# 2016-02-21_13-02-55.net
KiCad netlist of a schematic drawn in Altium Designer
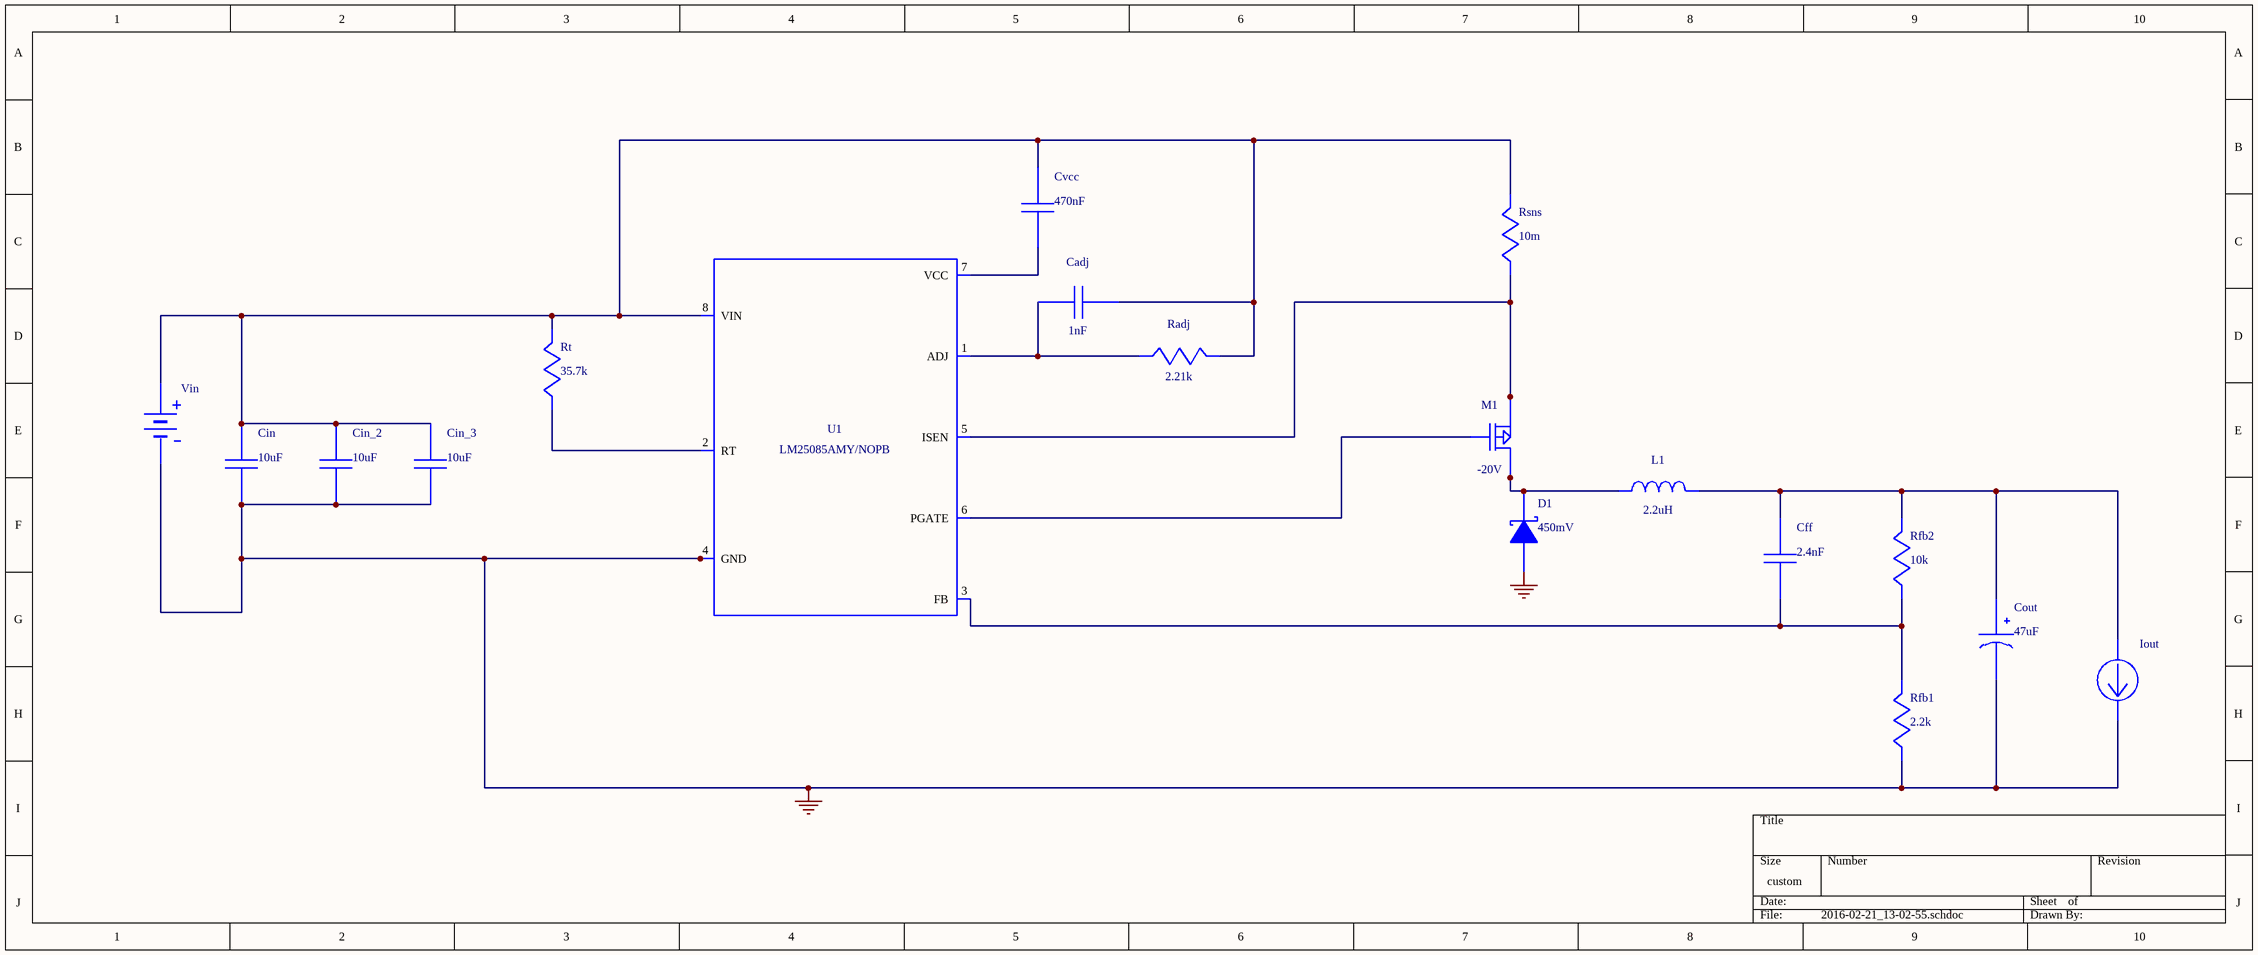
[diagram p0: 2016-02-21_13-02-55.schdoc]

(export (version "E")
  (design (tool "Eeschema 10.0.6"))
  (components
    (comp (ref "Cadj")
      (value "1nF")
      (description "CL21C102JBCNFNC")
      (libsource (lib "TI WEBENCH") (part "Cadj"))
    )
    (comp (ref "Cff")
      (value "2.4nF")
      (description "GRM1885C1H242JA0")
      (fields (field (name "MANUFACTURER PART NUMBER") "GRM1885C1H242JA01D"))
      (libsource (lib "TI WEBENCH") (part "Cff"))
    )
    (comp (ref "Cin")
      (value "10uF")
      (description "GRM21BR61C106KE1")
      (fields (field (name "MANUFACTURER PART NUMBER") "GRM21BR61C106KE15L"))
      (libsource (lib "TI WEBENCH") (part "Cin"))
    )
    (comp (ref "Cin_2")
      (value "10uF")
      (description "GRM21BR61C106KE1")
      (fields (field (name "MANUFACTURER PART NUMBER") "GRM21BR61C106KE15L"))
      (libsource (lib "TI WEBENCH") (part "Cin_2"))
    )
    (comp (ref "Cin_3")
      (value "10uF")
      (description "GRM21BR61C106KE1")
      (fields (field (name "MANUFACTURER PART NUMBER") "GRM21BR61C106KE15L"))
      (libsource (lib "TI WEBENCH") (part "Cin_3"))
    )
    (comp (ref "Cout") (value "47uF") (description "6TPU47MSI") (libsource (lib "TI WEBENCH") (part "Cout")))
    (comp (ref "Cvcc")
      (value "470nF")
      (description "0805YC474KAT2A")
      (libsource (lib "TI WEBENCH") (part "Cvcc"))
    )
    (comp (ref "D1") (value "450mV") (description "B340LA-13-F") (libsource (lib "TI WEBENCH") (part "D1")))
    (comp (ref "Iout") (value "WB_CURRENT_LOAD") (libsource (lib "TI WEBENCH") (part "Iout")))
    (comp (ref "L1")
      (value "2.2uH")
      (description "Unknown")
      (fields (field (name "MANUFACTURER PART NUMBER") "74437368022"))
      (libsource (lib "TI WEBENCH") (part "L1"))
    )
    (comp (ref "M1") (value "-20V") (description "CSD25402Q3A") (libsource (lib "TI WEBENCH") (part "M1")))
    (comp (ref "Radj")
      (value "2.21k")
      (description "CRCW04022K21FKED")
      (libsource (lib "TI WEBENCH") (part "Radj"))
    )
    (comp (ref "Rfb1")
      (value "2.2k")
      (description "RC0603FR-072K2L")
      (libsource (lib "TI WEBENCH") (part "Rfb1"))
    )
    (comp (ref "Rfb2")
      (value "10k")
      (description "CRCW040210K0FKED")
      (libsource (lib "TI WEBENCH") (part "Rfb2"))
    )
    (comp (ref "Rsns")
      (value "10m")
      (description "CSR1206FK10L0")
      (libsource (lib "TI WEBENCH") (part "Rsns"))
    )
    (comp (ref "Rt")
      (value "35.7k")
      (description "CRCW040235K7FKED")
      (libsource (lib "TI WEBENCH") (part "Rt"))
    )
    (comp (ref "U1")
      (value "LM5085MY/NOPB")
      (description "LM25085AMY/NOPB")
      (fields (field (name "PACKAGEREFERENCE") "LM25085AMY/NOPB"))
      (libsource (lib "TI WEBENCH") (part "U1"))
    )
    (comp (ref "Vin") (value "WB_BATTERY") (libsource (lib "TI WEBENCH") (part "Vin")))
  )
  (nets
    (net (code "1") (name "0") (class "Default")
      (node (ref "Cin") (pin "2") (pinfunction "2_2") (pintype "passive"))
      (node (ref "Cin_2") (pin "2") (pinfunction "2_2") (pintype "passive"))
      (node (ref "Cin_3") (pin "2") (pinfunction "2_2") (pintype "passive"))
      (node (ref "Cout") (pin "2") (pinfunction "-_2") (pintype "passive"))
      (node (ref "D1") (pin "2") (pinfunction "A_2") (pintype "passive"))
      (node (ref "Iout") (pin "2") (pinfunction "-_2") (pintype "passive"))
      (node (ref "Rfb1") (pin "2") (pinfunction "2_2") (pintype "passive"))
      (node (ref "U1") (pin "4") (pinfunction "GND_4") (pintype "passive"))
      (node (ref "U1") (pin "9") (pinfunction "EP_9") (pintype "passive"))
      (node (ref "Vin") (pin "2") (pinfunction "-_2") (pintype "passive"))
    )
    (net (code "2") (name "Net-(Cout-+)") (class "Default")
      (node (ref "Cff") (pin "1") (pinfunction "1_1") (pintype "passive"))
      (node (ref "Cout") (pin "1") (pinfunction "+_1") (pintype "passive"))
      (node (ref "Iout") (pin "1") (pinfunction "+_1") (pintype "passive"))
      (node (ref "L1") (pin "2") (pinfunction "2_2") (pintype "passive"))
      (node (ref "Rfb2") (pin "1") (pinfunction "1_1") (pintype "passive"))
    )
    (net (code "3") (name "Net-(D1-K)") (class "Default")
      (node (ref "D1") (pin "1") (pinfunction "K_1") (pintype "passive"))
      (node (ref "L1") (pin "1") (pinfunction "1_1") (pintype "passive"))
      (node (ref "M1") (pin "1") (pinfunction "D_1") (pintype "passive"))
      (node (ref "M1") (pin "2") (pinfunction "D_2") (pintype "passive"))
      (node (ref "M1") (pin "3") (pinfunction "D_3") (pintype "passive"))
    )
    (net (code "4") (name "Net-(M1-G)") (class "Default")
      (node (ref "M1") (pin "4") (pinfunction "G_4") (pintype "passive"))
      (node (ref "U1") (pin "6") (pinfunction "PGATE_6") (pintype "passive"))
    )
    (net (code "5") (name "Net-(U1-ADJ)") (class "Default")
      (node (ref "Cadj") (pin "2") (pinfunction "2_2") (pintype "passive"))
      (node (ref "Radj") (pin "2") (pinfunction "2_2") (pintype "passive"))
      (node (ref "U1") (pin "1") (pinfunction "ADJ_1") (pintype "passive"))
    )
    (net (code "6") (name "Net-(U1-FB)") (class "Default")
      (node (ref "Cff") (pin "2") (pinfunction "2_2") (pintype "passive"))
      (node (ref "Rfb1") (pin "1") (pinfunction "1_1") (pintype "passive"))
      (node (ref "Rfb2") (pin "2") (pinfunction "2_2") (pintype "passive"))
      (node (ref "U1") (pin "3") (pinfunction "FB_3") (pintype "passive"))
    )
    (net (code "7") (name "Net-(U1-ISEN)") (class "Default")
      (node (ref "M1") (pin "5") (pinfunction "S_5") (pintype "passive"))
      (node (ref "M1") (pin "6") (pinfunction "S_6") (pintype "passive"))
      (node (ref "M1") (pin "7") (pinfunction "S_7") (pintype "passive"))
      (node (ref "M1") (pin "8") (pinfunction "S_8") (pintype "passive"))
      (node (ref "M1") (pin "9") (pinfunction "S_9") (pintype "passive"))
      (node (ref "Rsns") (pin "2") (pinfunction "2_2") (pintype "passive"))
      (node (ref "U1") (pin "5") (pinfunction "ISEN_5") (pintype "passive"))
    )
    (net (code "8") (name "Net-(U1-RT)") (class "Default")
      (node (ref "Rt") (pin "2") (pinfunction "2_2") (pintype "passive"))
      (node (ref "U1") (pin "2") (pinfunction "RT_2") (pintype "passive"))
    )
    (net (code "9") (name "Net-(U1-VCC)") (class "Default")
      (node (ref "Cvcc") (pin "2") (pinfunction "2_2") (pintype "passive"))
      (node (ref "U1") (pin "7") (pinfunction "VCC_7") (pintype "passive"))
    )
    (net (code "10") (name "Net-(U1-VIN)") (class "Default")
      (node (ref "Cadj") (pin "1") (pinfunction "1_1") (pintype "passive"))
      (node (ref "Cin") (pin "1") (pinfunction "1_1") (pintype "passive"))
      (node (ref "Cin_2") (pin "1") (pinfunction "1_1") (pintype "passive"))
      (node (ref "Cin_3") (pin "1") (pinfunction "1_1") (pintype "passive"))
      (node (ref "Cvcc") (pin "1") (pinfunction "1_1") (pintype "passive"))
      (node (ref "Radj") (pin "1") (pinfunction "1_1") (pintype "passive"))
      (node (ref "Rsns") (pin "1") (pinfunction "1_1") (pintype "passive"))
      (node (ref "Rt") (pin "1") (pinfunction "1_1") (pintype "passive"))
      (node (ref "U1") (pin "8") (pinfunction "VIN_8") (pintype "passive"))
      (node (ref "Vin") (pin "1") (pinfunction "+_1") (pintype "passive"))
    )
  )
)
